# squall-blees-board.net
KiCad netlist of a schematic drawn in EAGLE
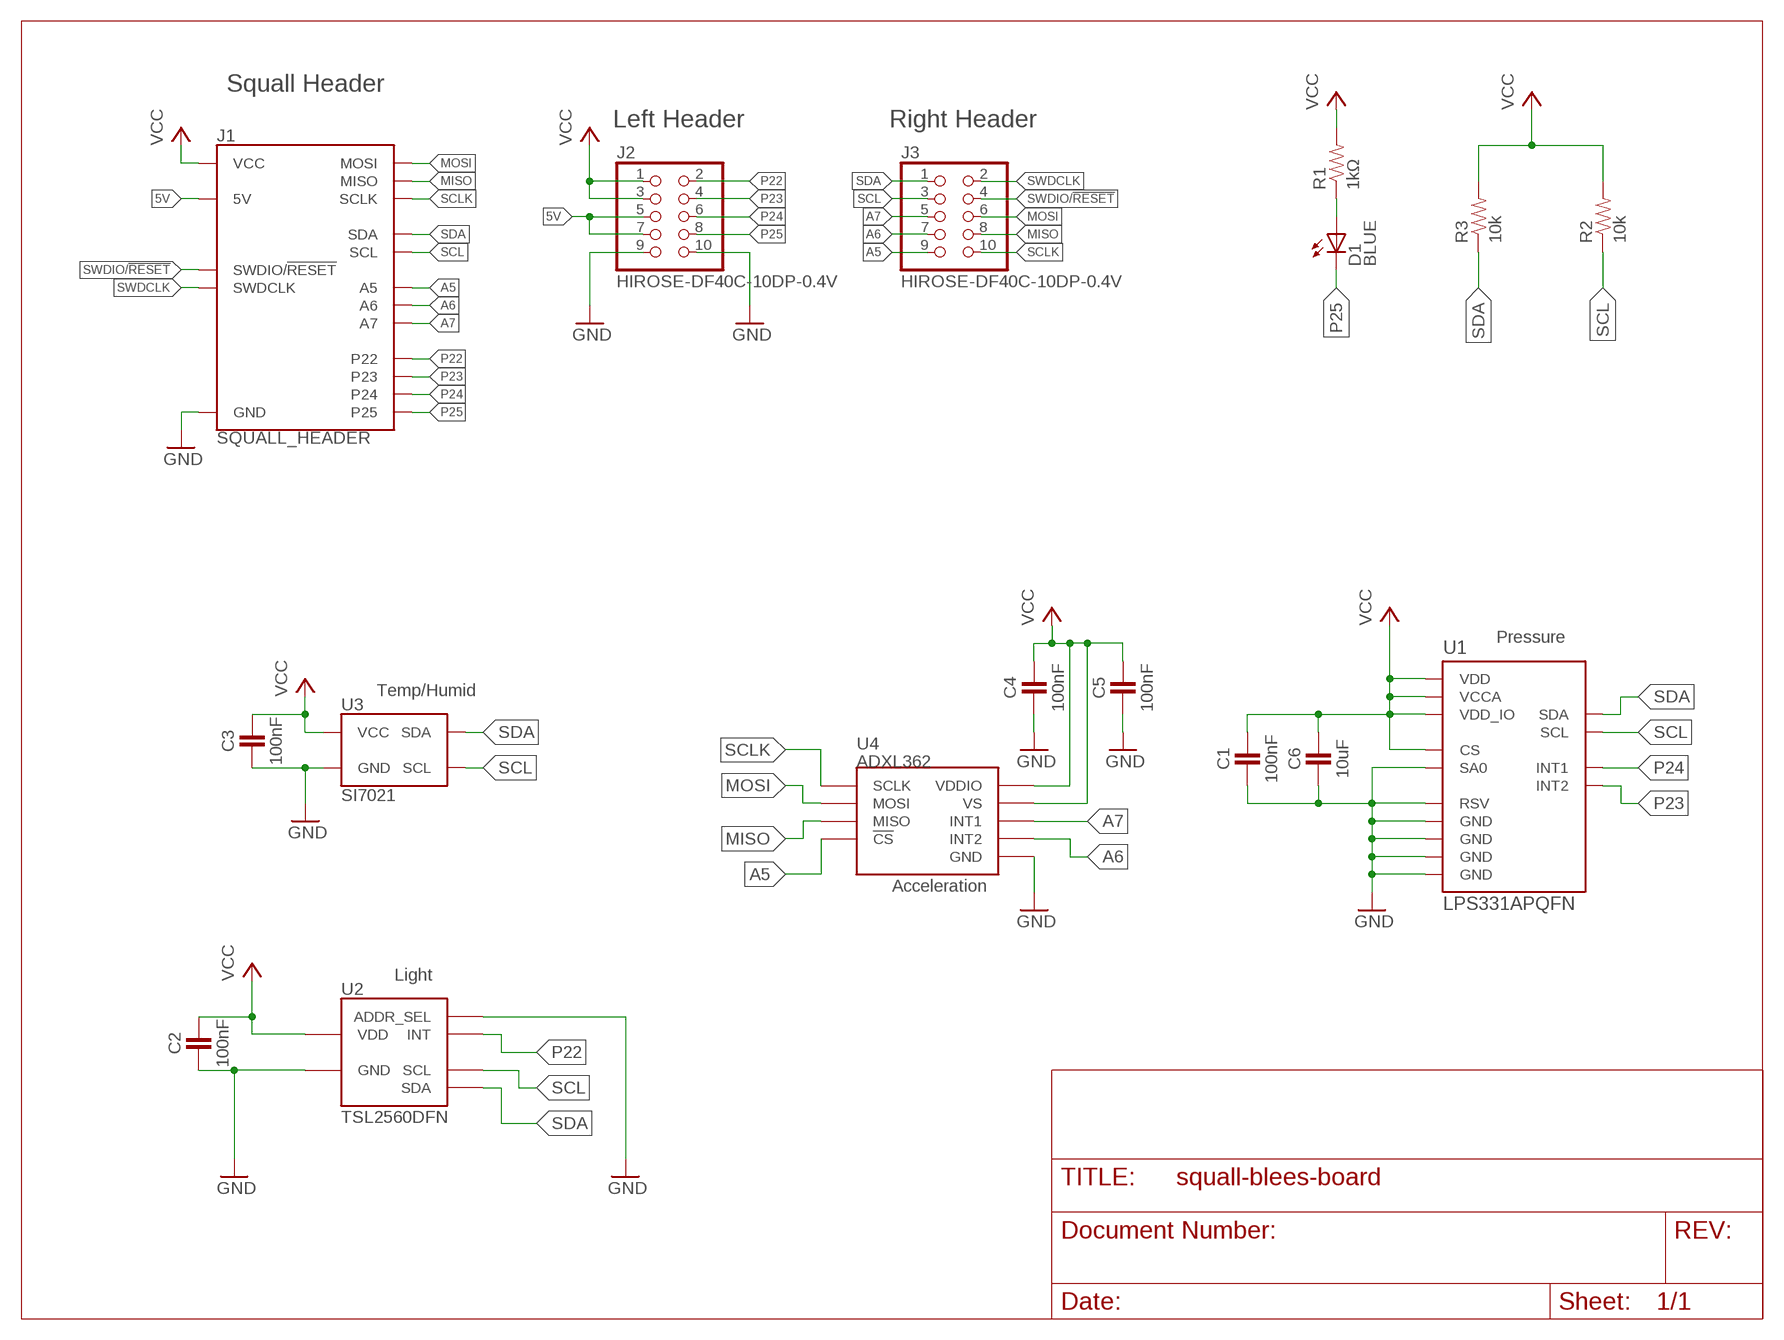
[diagram p0: schematic, sheet 1]

(export (version "E")
  (design (tool "Eeschema 10.0.6"))
  (components
    (comp (ref "C1")
      (value "100nF")
      (footprint "eagle-import:0402_CAP")
      (libsource (lib "eagle-import") (part "CAPACITOR"))
    )
    (comp (ref "C2")
      (value "100nF")
      (footprint "eagle-import:0402_CAP")
      (libsource (lib "eagle-import") (part "CAPACITOR"))
    )
    (comp (ref "C3")
      (value "100nF")
      (footprint "eagle-import:0402_CAP")
      (libsource (lib "eagle-import") (part "CAPACITOR"))
    )
    (comp (ref "C4")
      (value "100nF")
      (footprint "eagle-import:0402_CAP")
      (libsource (lib "eagle-import") (part "CAPACITOR"))
    )
    (comp (ref "C5")
      (value "100nF")
      (footprint "eagle-import:0402_CAP")
      (libsource (lib "eagle-import") (part "CAPACITOR"))
    )
    (comp (ref "C6")
      (value "10uF")
      (footprint "eagle-import:0603_CAP")
      (libsource (lib "eagle-import") (part "CAPACITOR0603_CAP"))
    )
    (comp (ref "D1")
      (value "BLUE")
      (footprint "eagle-import:LED-0603")
      (libsource (lib "eagle-import") (part "LED0603"))
    )
    (comp (ref "J1")
      (value "SQUALL_HEADER")
      (footprint "eagle-import:SQUALL_HEADER")
      (libsource (lib "eagle-import") (part "SQUALL_HEADER"))
    )
    (comp (ref "J2")
      (value "HIROSE-DF40C-10DP-0.4V")
      (footprint "eagle-import:2X5_SMD_0.4MM")
      (libsource (lib "eagle-import") (part "HIROSE-DF40C-10DP-0.4V"))
    )
    (comp (ref "J3")
      (value "HIROSE-DF40C-10DP-0.4V")
      (footprint "eagle-import:2X5_SMD_0.4MM")
      (libsource (lib "eagle-import") (part "HIROSE-DF40C-10DP-0.4V"))
    )
    (comp (ref "R1")
      (value "1kΩ")
      (footprint "eagle-import:0402_RES")
      (libsource (lib "eagle-import") (part "RESISTOR0402_RES"))
    )
    (comp (ref "R2")
      (value "10k")
      (footprint "eagle-import:0402_RES")
      (libsource (lib "eagle-import") (part "RESISTOR0402_RES"))
    )
    (comp (ref "R3")
      (value "10k")
      (footprint "eagle-import:0402_RES")
      (libsource (lib "eagle-import") (part "RESISTOR0402_RES"))
    )
    (comp (ref "U1")
      (value "LPS331APQFN")
      (footprint "eagle-import:HCLGA-16L")
      (libsource (lib "eagle-import") (part "LPS331APQFN"))
    )
    (comp (ref "U2")
      (value "TSL2560DFN")
      (footprint "eagle-import:DFN2")
      (libsource (lib "eagle-import") (part "TSL2560DFN"))
    )
    (comp (ref "U3")
      (value "SI7021")
      (footprint "eagle-import:DFN-6_3MM")
      (libsource (lib "eagle-import") (part "SI7021"))
    )
    (comp (ref "U4")
      (value "ADXL362")
      (footprint "eagle-import:ADXL362")
      (libsource (lib "eagle-import") (part "ADXL362"))
    )
  )
  (nets
    (net (code "1") (name "/SWDIO{slash}~{RESET}") (class "Default")
      (node (ref "J1") (pin "B4") (pinfunction "SWDIO/~{RESET}_B4") (pintype "bidirectional"))
      (node (ref "J3") (pin "4") (pinfunction "4_4") (pintype "passive"))
    )
    (net (code "2") (name "5V") (class "Default")
      (node (ref "J1") (pin "A5") (pinfunction "5V_A5") (pintype "bidirectional"))
      (node (ref "J1") (pin "A7") (pinfunction "5V_A7") (pintype "bidirectional"))
      (node (ref "J2") (pin "5") (pinfunction "5_5") (pintype "passive"))
      (node (ref "J2") (pin "7") (pinfunction "7_7") (pintype "passive"))
    )
    (net (code "3") (name "A5") (class "Default")
      (node (ref "J1") (pin "B9") (pinfunction "A5_B9") (pintype "bidirectional"))
      (node (ref "J3") (pin "9") (pinfunction "9_9") (pintype "passive"))
      (node (ref "U4") (pin "P$8") (pinfunction "~{CS}_P$8") (pintype "bidirectional"))
    )
    (net (code "4") (name "A6") (class "Default")
      (node (ref "J1") (pin "B7") (pinfunction "A6_B7") (pintype "bidirectional"))
      (node (ref "J3") (pin "7") (pinfunction "7_7") (pintype "passive"))
      (node (ref "U4") (pin "P$9") (pinfunction "INT2_P$9") (pintype "bidirectional"))
    )
    (net (code "5") (name "A7") (class "Default")
      (node (ref "J1") (pin "B5") (pinfunction "A7_B5") (pintype "bidirectional"))
      (node (ref "J3") (pin "5") (pinfunction "5_5") (pintype "passive"))
      (node (ref "U4") (pin "P$11") (pinfunction "INT1_P$11") (pintype "bidirectional"))
    )
    (net (code "6") (name "GND") (class "Default")
      (node (ref "C1") (pin "2") (pinfunction "2_2") (pintype "bidirectional"))
      (node (ref "C2") (pin "2") (pinfunction "2_2") (pintype "bidirectional"))
      (node (ref "C3") (pin "2") (pinfunction "2_2") (pintype "bidirectional"))
      (node (ref "C4") (pin "2") (pinfunction "2_2") (pintype "bidirectional"))
      (node (ref "C5") (pin "2") (pinfunction "2_2") (pintype "bidirectional"))
      (node (ref "C6") (pin "2") (pinfunction "2_2") (pintype "bidirectional"))
      (node (ref "J1") (pin "A10") (pinfunction "GND_A10") (pintype "bidirectional"))
      (node (ref "J1") (pin "A9") (pinfunction "GND_A9") (pintype "bidirectional"))
      (node (ref "J2") (pin "10") (pinfunction "10_10") (pintype "passive"))
      (node (ref "J2") (pin "9") (pinfunction "9_9") (pintype "passive"))
      (node (ref "U1") (pin "10") (pinfunction "RSV_10") (pintype "power_in"))
      (node (ref "U1") (pin "12") (pinfunction "GND_12") (pintype "power_in"))
      (node (ref "U1") (pin "13") (pinfunction "GND_13") (pintype "power_in"))
      (node (ref "U1") (pin "16") (pinfunction "GND_16") (pintype "power_in"))
      (node (ref "U1") (pin "5") (pinfunction "GND_5") (pintype "power_in"))
      (node (ref "U1") (pin "7") (pinfunction "SA0_7") (pintype "input"))
      (node (ref "U2") (pin "2") (pinfunction "ADDR_SEL_2") (pintype "bidirectional"))
      (node (ref "U2") (pin "3") (pinfunction "GND_3") (pintype "power_in"))
      (node (ref "U3") (pin "2") (pinfunction "GND_2") (pintype "bidirectional"))
      (node (ref "U4") (pin "P$12") (pinfunction "GND_P$12") (pintype "bidirectional"))
      (node (ref "U4") (pin "P$13") (pinfunction "GND_P$13") (pintype "bidirectional"))
      (node (ref "U4") (pin "P$16") (pinfunction "GND_P$16") (pintype "bidirectional"))
    )
    (net (code "7") (name "MISO") (class "Default")
      (node (ref "J1") (pin "B8") (pinfunction "MISO_B8") (pintype "bidirectional"))
      (node (ref "J3") (pin "8") (pinfunction "8_8") (pintype "passive"))
      (node (ref "U4") (pin "P$7") (pinfunction "MISO_P$7") (pintype "bidirectional"))
    )
    (net (code "8") (name "MOSI") (class "Default")
      (node (ref "J1") (pin "B6") (pinfunction "MOSI_B6") (pintype "bidirectional"))
      (node (ref "J3") (pin "6") (pinfunction "6_6") (pintype "passive"))
      (node (ref "U4") (pin "P$6") (pinfunction "MOSI_P$6") (pintype "bidirectional"))
    )
    (net (code "9") (name "Net-(D1-PadA)") (class "Default")
      (node (ref "D1") (pin "A") (pinfunction "A_A") (pintype "passive"))
      (node (ref "R1") (pin "1") (pinfunction "1_1") (pintype "passive"))
    )
    (net (code "10") (name "P22") (class "Default")
      (node (ref "J1") (pin "A2") (pinfunction "P22_A2") (pintype "bidirectional"))
      (node (ref "J2") (pin "2") (pinfunction "2_2") (pintype "passive"))
      (node (ref "U2") (pin "5") (pinfunction "INT_5") (pintype "bidirectional"))
    )
    (net (code "11") (name "P23") (class "Default")
      (node (ref "J1") (pin "A4") (pinfunction "P23_A4") (pintype "bidirectional"))
      (node (ref "J2") (pin "4") (pinfunction "4_4") (pintype "passive"))
      (node (ref "U1") (pin "9") (pinfunction "INT2_9") (pintype "bidirectional"))
    )
    (net (code "12") (name "P24") (class "Default")
      (node (ref "J1") (pin "A6") (pinfunction "P24_A6") (pintype "bidirectional"))
      (node (ref "J2") (pin "6") (pinfunction "6_6") (pintype "passive"))
      (node (ref "U1") (pin "11") (pinfunction "INT1_11") (pintype "bidirectional"))
    )
    (net (code "13") (name "P25") (class "Default")
      (node (ref "D1") (pin "C") (pinfunction "C_C") (pintype "passive"))
      (node (ref "J1") (pin "A8") (pinfunction "P25_A8") (pintype "bidirectional"))
      (node (ref "J2") (pin "8") (pinfunction "8_8") (pintype "passive"))
    )
    (net (code "14") (name "SCL") (class "Default")
      (node (ref "J1") (pin "B3") (pinfunction "SCL_B3") (pintype "bidirectional"))
      (node (ref "J3") (pin "3") (pinfunction "3_3") (pintype "passive"))
      (node (ref "R2") (pin "1") (pinfunction "1_1") (pintype "passive"))
      (node (ref "U1") (pin "4") (pinfunction "SCL_4") (pintype "bidirectional"))
      (node (ref "U2") (pin "4") (pinfunction "SCL_4") (pintype "bidirectional"))
      (node (ref "U3") (pin "6") (pinfunction "SCL_6") (pintype "bidirectional"))
    )
    (net (code "15") (name "SCLK") (class "Default")
      (node (ref "J1") (pin "B10") (pinfunction "SCLK_B10") (pintype "bidirectional"))
      (node (ref "J3") (pin "10") (pinfunction "10_10") (pintype "passive"))
      (node (ref "U4") (pin "P$4") (pinfunction "SCLK_P$4") (pintype "bidirectional"))
    )
    (net (code "16") (name "SDA") (class "Default")
      (node (ref "J1") (pin "B1") (pinfunction "SDA_B1") (pintype "bidirectional"))
      (node (ref "J3") (pin "1") (pinfunction "1_1") (pintype "passive"))
      (node (ref "R3") (pin "1") (pinfunction "1_1") (pintype "passive"))
      (node (ref "U1") (pin "6") (pinfunction "SDA_6") (pintype "bidirectional"))
      (node (ref "U2") (pin "6") (pinfunction "SDA_6") (pintype "bidirectional"))
      (node (ref "U3") (pin "1") (pinfunction "SDA_1") (pintype "bidirectional"))
    )
    (net (code "17") (name "SWDCLK") (class "Default")
      (node (ref "J1") (pin "B2") (pinfunction "SWDCLK_B2") (pintype "bidirectional"))
      (node (ref "J3") (pin "2") (pinfunction "2_2") (pintype "passive"))
    )
    (net (code "18") (name "VCC") (class "Default")
      (node (ref "C1") (pin "1") (pinfunction "1_1") (pintype "bidirectional"))
      (node (ref "C2") (pin "1") (pinfunction "1_1") (pintype "bidirectional"))
      (node (ref "C3") (pin "1") (pinfunction "1_1") (pintype "bidirectional"))
      (node (ref "C4") (pin "1") (pinfunction "1_1") (pintype "bidirectional"))
      (node (ref "C5") (pin "1") (pinfunction "1_1") (pintype "bidirectional"))
      (node (ref "C6") (pin "1") (pinfunction "1_1") (pintype "bidirectional"))
      (node (ref "J1") (pin "A1") (pinfunction "VCC_A1") (pintype "bidirectional"))
      (node (ref "J1") (pin "A3") (pinfunction "VCC_A3") (pintype "bidirectional"))
      (node (ref "J2") (pin "1") (pinfunction "1_1") (pintype "passive"))
      (node (ref "J2") (pin "3") (pinfunction "3_3") (pintype "passive"))
      (node (ref "R1") (pin "2") (pinfunction "2_2") (pintype "passive"))
      (node (ref "R2") (pin "2") (pinfunction "2_2") (pintype "passive"))
      (node (ref "R3") (pin "2") (pinfunction "2_2") (pintype "passive"))
      (node (ref "U1") (pin "1") (pinfunction "VDD_IO_1") (pintype "power_in"))
      (node (ref "U1") (pin "14") (pinfunction "VDD_14") (pintype "power_in"))
      (node (ref "U1") (pin "15") (pinfunction "VCCA_15") (pintype "power_in"))
      (node (ref "U1") (pin "8") (pinfunction "CS_8") (pintype "input"))
      (node (ref "U2") (pin "1") (pinfunction "VDD_1") (pintype "power_in"))
      (node (ref "U3") (pin "5") (pinfunction "VCC_5") (pintype "bidirectional"))
      (node (ref "U4") (pin "P$1") (pinfunction "VDDIO_P$1") (pintype "bidirectional"))
      (node (ref "U4") (pin "P$14") (pinfunction "VS_P$14") (pintype "bidirectional"))
    )
  )
)
